# SchematicDesign.net
KiCad netlist of a schematic drawn in Altium Designer
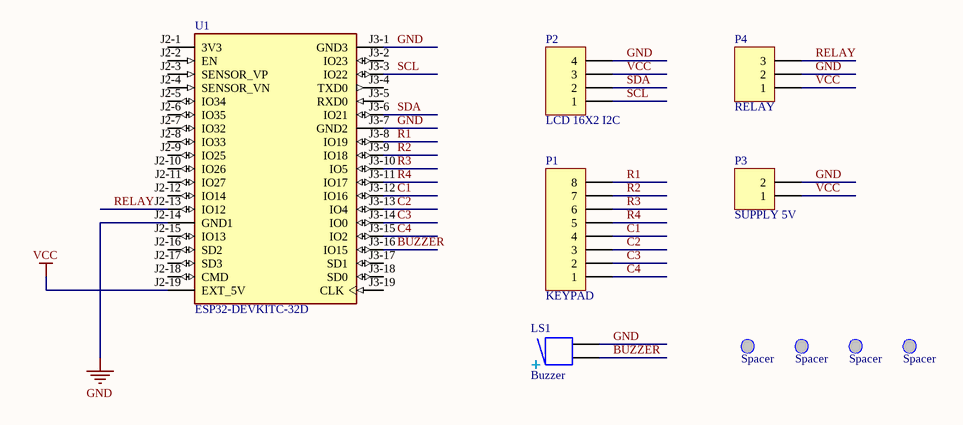
[diagram p0: SchematicDesign.SchDoc]

(export (version "E")
  (design (tool "Eeschema 10.0.6"))
  (components
    (comp (ref "1")
      (value "Spacer")
      (footprint "Spacer")
      (fields (field (name "PUBLISHER") "Altium Limited"))
      (libsource (lib "Custom") (part "Spacer"))
    )
    (comp (ref "2")
      (value "Spacer")
      (footprint "Spacer")
      (fields (field (name "PUBLISHER") "Altium Limited"))
      (libsource (lib "Custom") (part "Spacer"))
    )
    (comp (ref "3")
      (value "Spacer")
      (footprint "Spacer")
      (fields (field (name "PUBLISHER") "Altium Limited"))
      (libsource (lib "Custom") (part "Spacer"))
    )
    (comp (ref "4")
      (value "Spacer")
      (footprint "Spacer")
      (fields (field (name "PUBLISHER") "Altium Limited"))
      (libsource (lib "Custom") (part "Spacer"))
    )
    (comp (ref "LS1")
      (value "Buzzer")
      (footprint "BUZZER")
      (description "Magnetic Transducer Buzzer")
      (fields (field (name "PUBLISHER") "Altium Limited"))
      (libsource (lib "Ahahahahah Old") (part "Buzzer"))
    )
    (comp (ref "P1")
      (value "KEYPAD")
      (footprint "HDR1X8")
      (description "Header, 8-Pin")
      (fields (field (name "PUBLISHER") "Altium Limited"))
      (libsource (lib "Miscellaneous Connectors") (part "Header 8"))
    )
    (comp (ref "P2")
      (value "LCD 16X2 I2C")
      (footprint "HDR1X4")
      (description "Header, 4-Pin")
      (fields (field (name "PUBLISHER") "Altium Limited"))
      (libsource (lib "Miscellaneous Connectors") (part "Header 4"))
    )
    (comp (ref "P3")
      (value "SUPPLY 5V")
      (footprint "Term.Block 2pin")
      (description "Term.Block, 2-Pin")
      (fields (field (name "PUBLISHER") "Altium Limited"))
      (libsource (lib "Ahahahahah Old") (part "Term.Block 2pin"))
    )
    (comp (ref "P4")
      (value "RELAY")
      (footprint "HDR1X3")
      (description "Header, 3-Pin")
      (fields (field (name "PUBLISHER") "Altium Limited"))
      (libsource (lib "Miscellaneous Connectors") (part "Header 3"))
    )
    (comp (ref "U1")
      (value "ESP32-DEVKITC-32D")
      (footprint "MODULE_ESP32-DEVKITC-32D")
      (description "WiFi Development Tools (802.11) ESP32 General Development Kit, ESP32-WROOM-32D on the board")
      (fields (field (name "MF") "Espressif Systems"))
      (libsource (lib "ESP32-DEVKITC-32D") (part "ESP32-DEVKITC-32D"))
    )
  )
  (nets
    (net (code "1") (name "/BUZZER") (class "Default")
      (node (ref "LS1") (pin "1") (pinfunction "1_1") (pintype "passive"))
      (node (ref "U1") (pin "J3-16") (pinfunction "IO15_J3-16") (pintype "bidirectional"))
    )
    (net (code "2") (name "/C1") (class "Default")
      (node (ref "P1") (pin "4") (pinfunction "4_4") (pintype "passive"))
      (node (ref "U1") (pin "J3-12") (pinfunction "IO16_J3-12") (pintype "bidirectional"))
    )
    (net (code "3") (name "/C2") (class "Default")
      (node (ref "P1") (pin "3") (pinfunction "3_3") (pintype "passive"))
      (node (ref "U1") (pin "J3-13") (pinfunction "IO4_J3-13") (pintype "bidirectional"))
    )
    (net (code "4") (name "/C3") (class "Default")
      (node (ref "P1") (pin "2") (pinfunction "2_2") (pintype "passive"))
      (node (ref "U1") (pin "J3-14") (pinfunction "IO0_J3-14") (pintype "bidirectional"))
    )
    (net (code "5") (name "/C4") (class "Default")
      (node (ref "P1") (pin "1") (pinfunction "1_1") (pintype "passive"))
      (node (ref "U1") (pin "J3-15") (pinfunction "IO2_J3-15") (pintype "bidirectional"))
    )
    (net (code "6") (name "/R1") (class "Default")
      (node (ref "P1") (pin "8") (pinfunction "8_8") (pintype "passive"))
      (node (ref "U1") (pin "J3-8") (pinfunction "IO19_J3-8") (pintype "bidirectional"))
    )
    (net (code "7") (name "/R2") (class "Default")
      (node (ref "P1") (pin "7") (pinfunction "7_7") (pintype "passive"))
      (node (ref "U1") (pin "J3-9") (pinfunction "IO18_J3-9") (pintype "bidirectional"))
    )
    (net (code "8") (name "/R3") (class "Default")
      (node (ref "P1") (pin "6") (pinfunction "6_6") (pintype "passive"))
      (node (ref "U1") (pin "J3-10") (pinfunction "IO5_J3-10") (pintype "bidirectional"))
    )
    (net (code "9") (name "/R4") (class "Default")
      (node (ref "P1") (pin "5") (pinfunction "5_5") (pintype "passive"))
      (node (ref "U1") (pin "J3-11") (pinfunction "IO17_J3-11") (pintype "bidirectional"))
    )
    (net (code "10") (name "/RELAY") (class "Default")
      (node (ref "P4") (pin "3") (pinfunction "3_3") (pintype "passive"))
      (node (ref "U1") (pin "J2-13") (pinfunction "IO12_J2-13") (pintype "bidirectional"))
    )
    (net (code "11") (name "/SCL") (class "Default")
      (node (ref "P2") (pin "1") (pinfunction "1_1") (pintype "passive"))
      (node (ref "U1") (pin "J3-3") (pinfunction "IO22_J3-3") (pintype "bidirectional"))
    )
    (net (code "12") (name "/SDA") (class "Default")
      (node (ref "P2") (pin "2") (pinfunction "2_2") (pintype "passive"))
      (node (ref "U1") (pin "J3-6") (pinfunction "IO21_J3-6") (pintype "bidirectional"))
    )
    (net (code "13") (name "GND") (class "Default")
      (node (ref "LS1") (pin "2") (pinfunction "2_2") (pintype "passive"))
      (node (ref "P2") (pin "4") (pinfunction "4_4") (pintype "passive"))
      (node (ref "P3") (pin "1") (pinfunction "2_1") (pintype "passive"))
      (node (ref "P4") (pin "2") (pinfunction "2_2") (pintype "passive"))
      (node (ref "U1") (pin "J2-14") (pinfunction "GND1_J2-14") (pintype "power_in"))
      (node (ref "U1") (pin "J3-1") (pinfunction "GND3_J3-1") (pintype "power_in"))
      (node (ref "U1") (pin "J3-7") (pinfunction "GND2_J3-7") (pintype "power_in"))
    )
    (net (code "14") (name "VCC") (class "Default")
      (node (ref "P2") (pin "3") (pinfunction "3_3") (pintype "passive"))
      (node (ref "P3") (pin "0") (pinfunction "1_0") (pintype "passive"))
      (node (ref "P4") (pin "1") (pinfunction "1_1") (pintype "passive"))
      (node (ref "U1") (pin "J2-19") (pinfunction "EXT_5V_J2-19") (pintype "power_in"))
    )
    (net (code "15") (name "unconnected-(U1-3V3-PadJ2-1)") (class "Default")
      (node (ref "U1") (pin "J2-1") (pinfunction "3V3_J2-1") (pintype "power_in"))
    )
    (net (code "16") (name "unconnected-(U1-CLK-PadJ3-19)") (class "Default")
      (node (ref "U1") (pin "J3-19") (pinfunction "CLK_J3-19") (pintype "input"))
    )
    (net (code "17") (name "unconnected-(U1-CMD-PadJ2-18)") (class "Default")
      (node (ref "U1") (pin "J2-18") (pinfunction "CMD_J2-18") (pintype "bidirectional"))
    )
    (net (code "18") (name "unconnected-(U1-EN-PadJ2-2)") (class "Default")
      (node (ref "U1") (pin "J2-2") (pinfunction "EN_J2-2") (pintype "input"))
    )
    (net (code "19") (name "unconnected-(U1-IO13-PadJ2-15)") (class "Default")
      (node (ref "U1") (pin "J2-15") (pinfunction "IO13_J2-15") (pintype "bidirectional"))
    )
    (net (code "20") (name "unconnected-(U1-IO14-PadJ2-12)") (class "Default")
      (node (ref "U1") (pin "J2-12") (pinfunction "IO14_J2-12") (pintype "bidirectional"))
    )
    (net (code "21") (name "unconnected-(U1-IO23-PadJ3-2)") (class "Default")
      (node (ref "U1") (pin "J3-2") (pinfunction "IO23_J3-2") (pintype "bidirectional"))
    )
    (net (code "22") (name "unconnected-(U1-IO25-PadJ2-9)") (class "Default")
      (node (ref "U1") (pin "J2-9") (pinfunction "IO25_J2-9") (pintype "bidirectional"))
    )
    (net (code "23") (name "unconnected-(U1-IO26-PadJ2-10)") (class "Default")
      (node (ref "U1") (pin "J2-10") (pinfunction "IO26_J2-10") (pintype "bidirectional"))
    )
    (net (code "24") (name "unconnected-(U1-IO27-PadJ2-11)") (class "Default")
      (node (ref "U1") (pin "J2-11") (pinfunction "IO27_J2-11") (pintype "bidirectional"))
    )
    (net (code "25") (name "unconnected-(U1-IO32-PadJ2-7)") (class "Default")
      (node (ref "U1") (pin "J2-7") (pinfunction "IO32_J2-7") (pintype "bidirectional"))
    )
    (net (code "26") (name "unconnected-(U1-IO33-PadJ2-8)") (class "Default")
      (node (ref "U1") (pin "J2-8") (pinfunction "IO33_J2-8") (pintype "bidirectional"))
    )
    (net (code "27") (name "unconnected-(U1-IO34-PadJ2-5)") (class "Default")
      (node (ref "U1") (pin "J2-5") (pinfunction "IO34_J2-5") (pintype "bidirectional"))
    )
    (net (code "28") (name "unconnected-(U1-IO35-PadJ2-6)") (class "Default")
      (node (ref "U1") (pin "J2-6") (pinfunction "IO35_J2-6") (pintype "bidirectional"))
    )
    (net (code "29") (name "unconnected-(U1-RXD0-PadJ3-5)") (class "Default")
      (node (ref "U1") (pin "J3-5") (pinfunction "RXD0_J3-5") (pintype "input"))
    )
    (net (code "30") (name "unconnected-(U1-SD0-PadJ3-18)") (class "Default")
      (node (ref "U1") (pin "J3-18") (pinfunction "SD0_J3-18") (pintype "bidirectional"))
    )
    (net (code "31") (name "unconnected-(U1-SD1-PadJ3-17)") (class "Default")
      (node (ref "U1") (pin "J3-17") (pinfunction "SD1_J3-17") (pintype "bidirectional"))
    )
    (net (code "32") (name "unconnected-(U1-SD2-PadJ2-16)") (class "Default")
      (node (ref "U1") (pin "J2-16") (pinfunction "SD2_J2-16") (pintype "bidirectional"))
    )
    (net (code "33") (name "unconnected-(U1-SD3-PadJ2-17)") (class "Default")
      (node (ref "U1") (pin "J2-17") (pinfunction "SD3_J2-17") (pintype "bidirectional"))
    )
    (net (code "34") (name "unconnected-(U1-SENSOR_VN-PadJ2-4)") (class "Default")
      (node (ref "U1") (pin "J2-4") (pinfunction "SENSOR_VN_J2-4") (pintype "input"))
    )
    (net (code "35") (name "unconnected-(U1-SENSOR_VP-PadJ2-3)") (class "Default")
      (node (ref "U1") (pin "J2-3") (pinfunction "SENSOR_VP_J2-3") (pintype "input"))
    )
    (net (code "36") (name "unconnected-(U1-TXD0-PadJ3-4)") (class "Default")
      (node (ref "U1") (pin "J3-4") (pinfunction "TXD0_J3-4") (pintype "output"))
    )
  )
)
